# hashlet_bbb.net
KiCad netlist of a schematic drawn in EAGLE
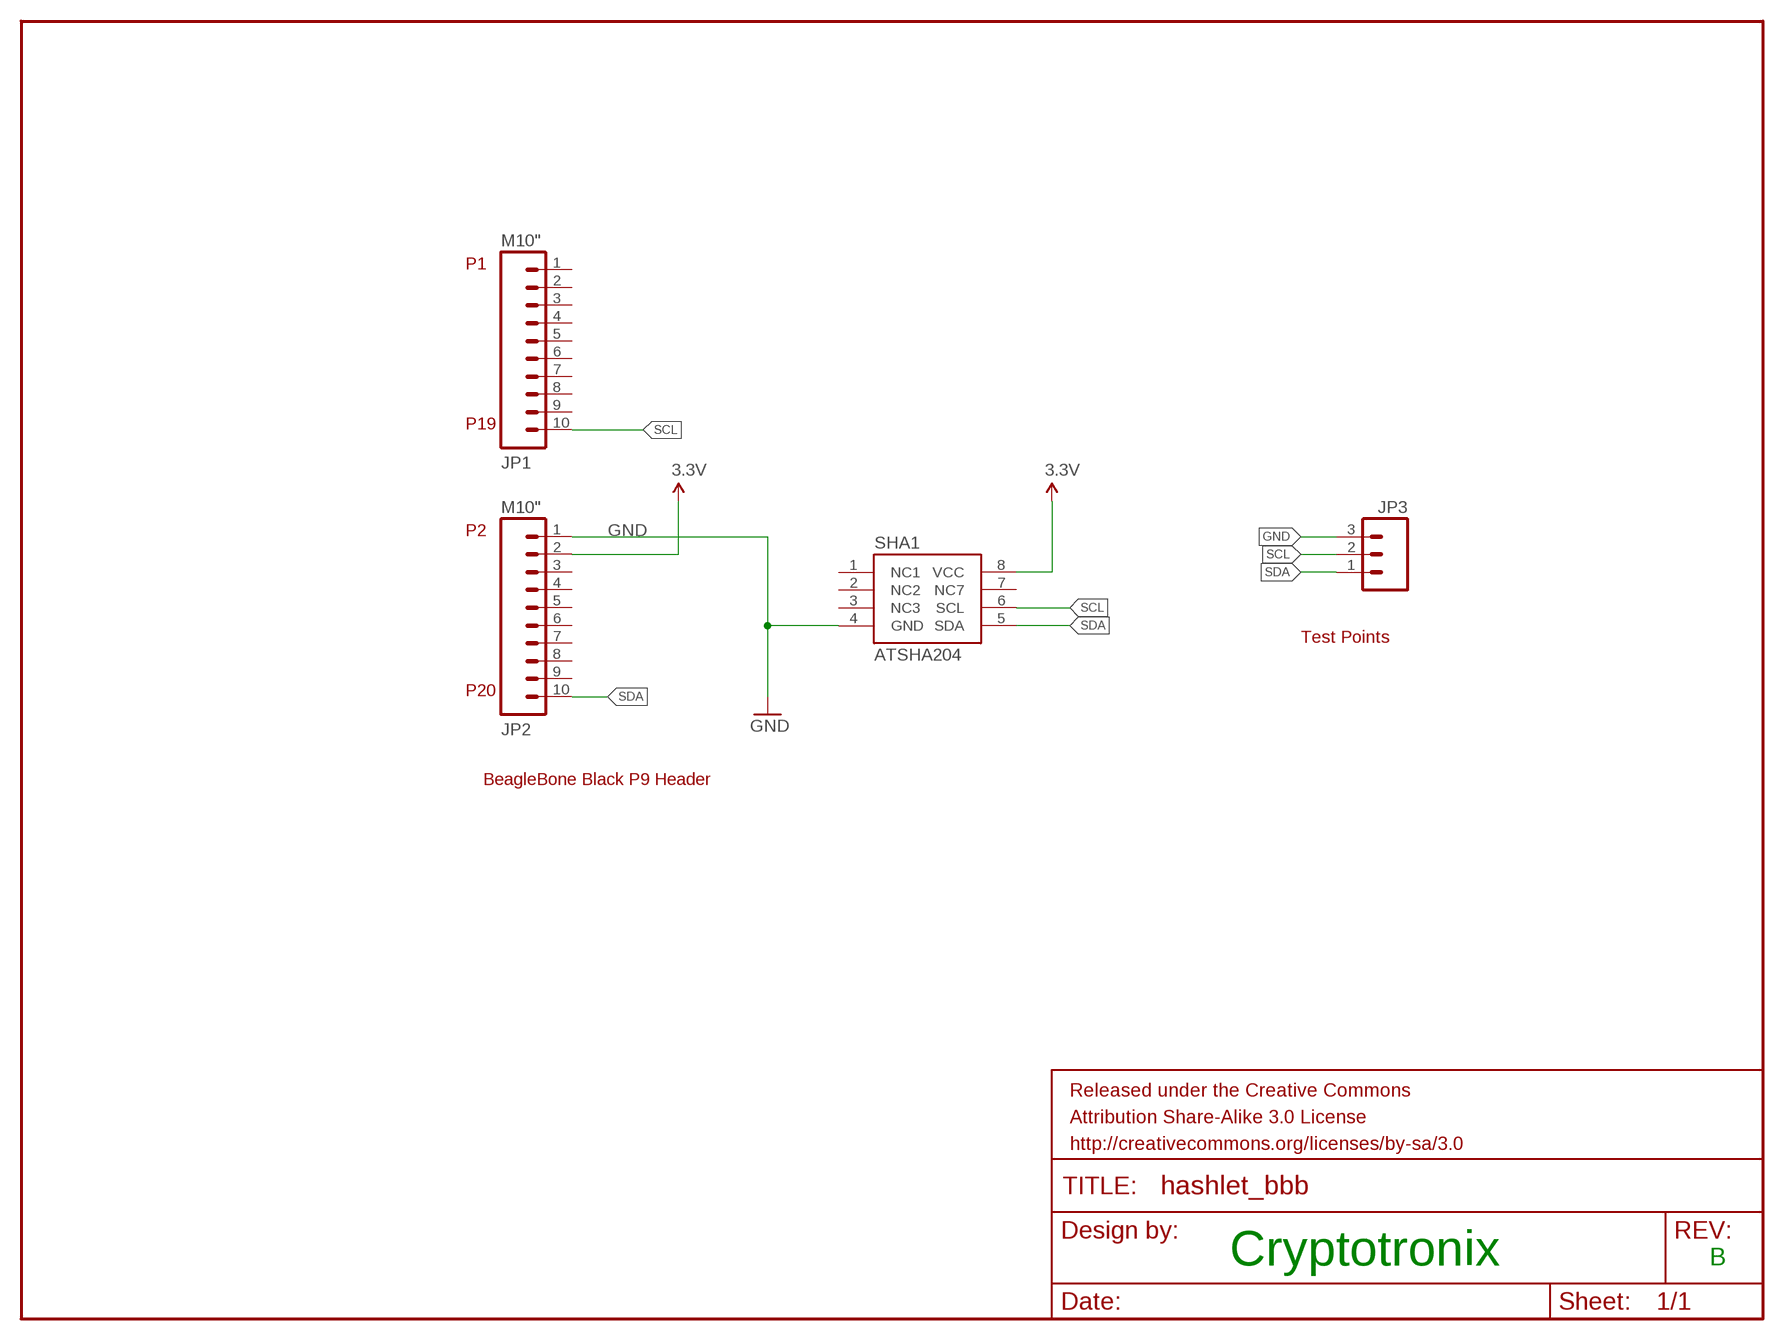
[diagram p0: schematic, sheet 1]

(export (version "E")
  (design (tool "Eeschema 10.0.6"))
  (components
    (comp (ref "FRAME1")
      (value "FRAME-LETTER")
      (footprint "eagle-import:CREATIVE_COMMONS")
      (libsource (lib "eagle-import") (part "FRAME-LETTER"))
    )
    (comp (ref "JP1")
      (value "M10\"")
      (footprint "eagle-import:1X10")
      (libsource (lib "eagle-import") (part "M10{dblquote}"))
    )
    (comp (ref "JP2")
      (value "M10\"")
      (footprint "eagle-import:1X10")
      (libsource (lib "eagle-import") (part "M10{dblquote}"))
    )
    (comp (ref "JP3")
      (value "M03PTH")
      (footprint "eagle-import:1X03")
      (libsource (lib "eagle-import") (part "M03PTH"))
    )
    (comp (ref "SHA1")
      (value "ATSHA204")
      (footprint "eagle-import:SOIC8")
      (libsource (lib "eagle-import") (part "ATSHA204"))
    )
  )
  (nets
    (net (code "1") (name "3.3V") (class "Default")
      (node (ref "JP2") (pin "2") (pinfunction "2_2") (pintype "passive"))
      (node (ref "SHA1") (pin "8") (pinfunction "VCC_8") (pintype "power_in"))
    )
    (net (code "2") (name "GND") (class "Default")
      (node (ref "JP2") (pin "1") (pinfunction "1_1") (pintype "passive"))
      (node (ref "JP3") (pin "3") (pinfunction "3_3") (pintype "passive"))
      (node (ref "SHA1") (pin "4") (pinfunction "GND_4") (pintype "power_in"))
    )
    (net (code "3") (name "SCL") (class "Default")
      (node (ref "JP1") (pin "10") (pinfunction "10_10") (pintype "passive"))
      (node (ref "JP3") (pin "2") (pinfunction "2_2") (pintype "passive"))
      (node (ref "SHA1") (pin "6") (pinfunction "SCL_6") (pintype "bidirectional"))
    )
    (net (code "4") (name "SDA") (class "Default")
      (node (ref "JP2") (pin "10") (pinfunction "10_10") (pintype "passive"))
      (node (ref "JP3") (pin "1") (pinfunction "1_1") (pintype "passive"))
      (node (ref "SHA1") (pin "5") (pinfunction "SDA_5") (pintype "bidirectional"))
    )
    (net (code "5") (name "unconnected-(JP1-Pad1)") (class "Default")
      (node (ref "JP1") (pin "1") (pinfunction "1_1") (pintype "passive"))
    )
    (net (code "6") (name "unconnected-(JP1-Pad2)") (class "Default")
      (node (ref "JP1") (pin "2") (pinfunction "2_2") (pintype "passive"))
    )
    (net (code "7") (name "unconnected-(JP1-Pad3)") (class "Default")
      (node (ref "JP1") (pin "3") (pinfunction "3_3") (pintype "passive"))
    )
    (net (code "8") (name "unconnected-(JP1-Pad4)") (class "Default")
      (node (ref "JP1") (pin "4") (pinfunction "4_4") (pintype "passive"))
    )
    (net (code "9") (name "unconnected-(JP1-Pad5)") (class "Default")
      (node (ref "JP1") (pin "5") (pinfunction "5_5") (pintype "passive"))
    )
    (net (code "10") (name "unconnected-(JP1-Pad6)") (class "Default")
      (node (ref "JP1") (pin "6") (pinfunction "6_6") (pintype "passive"))
    )
    (net (code "11") (name "unconnected-(JP1-Pad7)") (class "Default")
      (node (ref "JP1") (pin "7") (pinfunction "7_7") (pintype "passive"))
    )
    (net (code "12") (name "unconnected-(JP1-Pad8)") (class "Default")
      (node (ref "JP1") (pin "8") (pinfunction "8_8") (pintype "passive"))
    )
    (net (code "13") (name "unconnected-(JP1-Pad9)") (class "Default")
      (node (ref "JP1") (pin "9") (pinfunction "9_9") (pintype "passive"))
    )
    (net (code "14") (name "unconnected-(JP2-Pad3)") (class "Default")
      (node (ref "JP2") (pin "3") (pinfunction "3_3") (pintype "passive"))
    )
    (net (code "15") (name "unconnected-(JP2-Pad4)") (class "Default")
      (node (ref "JP2") (pin "4") (pinfunction "4_4") (pintype "passive"))
    )
    (net (code "16") (name "unconnected-(JP2-Pad5)") (class "Default")
      (node (ref "JP2") (pin "5") (pinfunction "5_5") (pintype "passive"))
    )
    (net (code "17") (name "unconnected-(JP2-Pad6)") (class "Default")
      (node (ref "JP2") (pin "6") (pinfunction "6_6") (pintype "passive"))
    )
    (net (code "18") (name "unconnected-(JP2-Pad7)") (class "Default")
      (node (ref "JP2") (pin "7") (pinfunction "7_7") (pintype "passive"))
    )
    (net (code "19") (name "unconnected-(JP2-Pad8)") (class "Default")
      (node (ref "JP2") (pin "8") (pinfunction "8_8") (pintype "passive"))
    )
    (net (code "20") (name "unconnected-(JP2-Pad9)") (class "Default")
      (node (ref "JP2") (pin "9") (pinfunction "9_9") (pintype "passive"))
    )
    (net (code "21") (name "unconnected-(SHA1-NC1-Pad1)") (class "Default")
      (node (ref "SHA1") (pin "1") (pinfunction "NC1_1") (pintype "no_connect"))
    )
    (net (code "22") (name "unconnected-(SHA1-NC2-Pad2)") (class "Default")
      (node (ref "SHA1") (pin "2") (pinfunction "NC2_2") (pintype "no_connect"))
    )
    (net (code "23") (name "unconnected-(SHA1-NC3-Pad3)") (class "Default")
      (node (ref "SHA1") (pin "3") (pinfunction "NC3_3") (pintype "no_connect"))
    )
    (net (code "24") (name "unconnected-(SHA1-NC7-Pad7)") (class "Default")
      (node (ref "SHA1") (pin "7") (pinfunction "NC7_7") (pintype "no_connect"))
    )
  )
)
